# PCIe-JTAG.net
KiCad netlist of a schematic drawn in Altium Designer
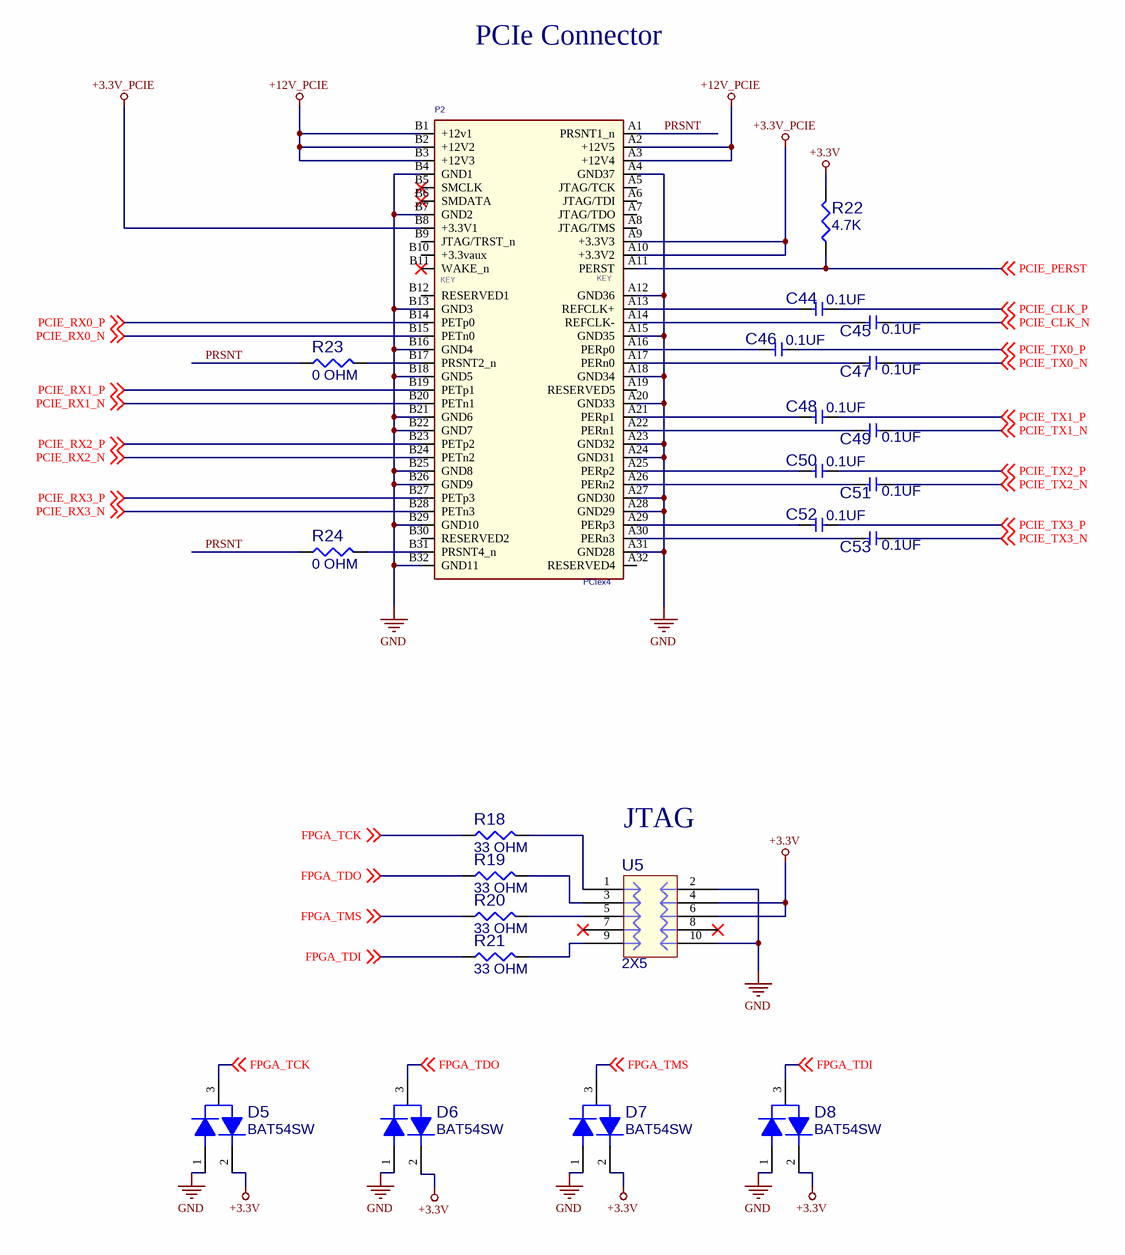
[diagram p0: PCIe-JTAG.SchDoc]

(export (version "E")
  (design (tool "Eeschema 10.0.6"))
  (components
    (comp (ref "C44")
      (value "0.1UF")
      (footprint "CAPC1005X06N")
      (description "CAP, CER, 0.1UF, 50V, 10%, X7R, AEC-Q200, 0402")
      (fields
        (field (name "MFG PART NUM") "CGA2B3X7R1H104K050BB")
        (field (name "VALENTIUM PART NUM") "<VALENTIUM>")
      )
      (libsource (lib "Capacitors") (part "CAP_0402_0.1UF_50V"))
    )
    (comp (ref "C45")
      (value "0.1UF")
      (footprint "CAPC1005X06N")
      (description "CAP, CER, 0.1UF, 50V, 10%, X7R, AEC-Q200, 0402")
      (fields
        (field (name "MFG PART NUM") "CGA2B3X7R1H104K050BB")
        (field (name "VALENTIUM PART NUM") "<VALENTIUM>")
      )
      (libsource (lib "Capacitors") (part "CAP_0402_0.1UF_50V"))
    )
    (comp (ref "C46")
      (value "0.1UF")
      (footprint "CAPC1005X06N")
      (description "CAP, CER, 0.1UF, 50V, 10%, X7R, AEC-Q200, 0402")
      (fields
        (field (name "MFG PART NUM") "CGA2B3X7R1H104K050BB")
        (field (name "VALENTIUM PART NUM") "<VALENTIUM>")
      )
      (libsource (lib "Capacitors") (part "CAP_0402_0.1UF_50V"))
    )
    (comp (ref "C47")
      (value "0.1UF")
      (footprint "CAPC1005X06N")
      (description "CAP, CER, 0.1UF, 50V, 10%, X7R, AEC-Q200, 0402")
      (fields
        (field (name "MFG PART NUM") "CGA2B3X7R1H104K050BB")
        (field (name "VALENTIUM PART NUM") "<VALENTIUM>")
      )
      (libsource (lib "Capacitors") (part "CAP_0402_0.1UF_50V"))
    )
    (comp (ref "C48")
      (value "0.1UF")
      (footprint "CAPC1005X06N")
      (description "CAP, CER, 0.1UF, 50V, 10%, X7R, AEC-Q200, 0402")
      (fields
        (field (name "MFG PART NUM") "CGA2B3X7R1H104K050BB")
        (field (name "VALENTIUM PART NUM") "<VALENTIUM>")
      )
      (libsource (lib "Capacitors") (part "CAP_0402_0.1UF_50V"))
    )
    (comp (ref "C49")
      (value "0.1UF")
      (footprint "CAPC1005X06N")
      (description "CAP, CER, 0.1UF, 50V, 10%, X7R, AEC-Q200, 0402")
      (fields
        (field (name "MFG PART NUM") "CGA2B3X7R1H104K050BB")
        (field (name "VALENTIUM PART NUM") "<VALENTIUM>")
      )
      (libsource (lib "Capacitors") (part "CAP_0402_0.1UF_50V"))
    )
    (comp (ref "C50")
      (value "0.1UF")
      (footprint "CAPC1005X06N")
      (description "CAP, CER, 0.1UF, 50V, 10%, X7R, AEC-Q200, 0402")
      (fields
        (field (name "MFG PART NUM") "CGA2B3X7R1H104K050BB")
        (field (name "VALENTIUM PART NUM") "<VALENTIUM>")
      )
      (libsource (lib "Capacitors") (part "CAP_0402_0.1UF_50V"))
    )
    (comp (ref "C51")
      (value "0.1UF")
      (footprint "CAPC1005X06N")
      (description "CAP, CER, 0.1UF, 50V, 10%, X7R, AEC-Q200, 0402")
      (fields
        (field (name "MFG PART NUM") "CGA2B3X7R1H104K050BB")
        (field (name "VALENTIUM PART NUM") "<VALENTIUM>")
      )
      (libsource (lib "Capacitors") (part "CAP_0402_0.1UF_50V"))
    )
    (comp (ref "C52")
      (value "0.1UF")
      (footprint "CAPC1005X06N")
      (description "CAP, CER, 0.1UF, 50V, 10%, X7R, AEC-Q200, 0402")
      (fields
        (field (name "MFG PART NUM") "CGA2B3X7R1H104K050BB")
        (field (name "VALENTIUM PART NUM") "<VALENTIUM>")
      )
      (libsource (lib "Capacitors") (part "CAP_0402_0.1UF_50V"))
    )
    (comp (ref "C53")
      (value "0.1UF")
      (footprint "CAPC1005X06N")
      (description "CAP, CER, 0.1UF, 50V, 10%, X7R, AEC-Q200, 0402")
      (fields
        (field (name "MFG PART NUM") "CGA2B3X7R1H104K050BB")
        (field (name "VALENTIUM PART NUM") "<VALENTIUM>")
      )
      (libsource (lib "Capacitors") (part "CAP_0402_0.1UF_50V"))
    )
    (comp (ref "D5")
      (value "BAT54SW")
      (footprint "SOT65P210X110-3N")
      (description "DIO, SCHOTTKY, BAT54S, DUAL SERIES, 30V, 200MA, SC-70")
      (fields (field (name "MFG PART NUM") "BAT54SWQ-7-F") (field (name "VALENTIUM PART NUM") "<VALENTIUM>"))
      (libsource (lib "Passives") (part "BAT54SW"))
    )
    (comp (ref "D6")
      (value "BAT54SW")
      (footprint "SOT65P210X110-3N")
      (description "DIO, SCHOTTKY, BAT54S, DUAL SERIES, 30V, 200MA, SC-70")
      (fields (field (name "MFG PART NUM") "BAT54SWQ-7-F") (field (name "VALENTIUM PART NUM") "<VALENTIUM>"))
      (libsource (lib "Passives") (part "BAT54SW"))
    )
    (comp (ref "D7")
      (value "BAT54SW")
      (footprint "SOT65P210X110-3N")
      (description "DIO, SCHOTTKY, BAT54S, DUAL SERIES, 30V, 200MA, SC-70")
      (fields (field (name "MFG PART NUM") "BAT54SWQ-7-F") (field (name "VALENTIUM PART NUM") "<VALENTIUM>"))
      (libsource (lib "Passives") (part "BAT54SW"))
    )
    (comp (ref "D8")
      (value "BAT54SW")
      (footprint "SOT65P210X110-3N")
      (description "DIO, SCHOTTKY, BAT54S, DUAL SERIES, 30V, 200MA, SC-70")
      (fields (field (name "MFG PART NUM") "BAT54SWQ-7-F") (field (name "VALENTIUM PART NUM") "<VALENTIUM>"))
      (libsource (lib "Passives") (part "BAT54SW"))
    )
    (comp (ref "P2")
      (value "PCIex4")
      (footprint "PCIE_4LANE_EDGE")
      (description "PCIE x4 Edge Connector,OrCAD Symbol,NC")
      (fields (field (name "PART NUMBER") "451") (field (name "MANUFACTURER") "NA"))
      (libsource (lib "Connectors") (part "PCIex4"))
    )
    (comp (ref "R18")
      (value "33 OHM")
      (footprint "RESC2012X50N")
      (description "RES, 33 OHM, 1%, 1/8W, TF, 0805")
      (fields
        (field (name "MFG PART NUM") "CRCW080533R0FKEA")
        (field (name "VELENTIUM PART NUM") "<VELENTIUM>")
      )
      (libsource (lib "Resistors") (part "RES_0805_33"))
    )
    (comp (ref "R19")
      (value "33 OHM")
      (footprint "RESC2012X50N")
      (description "RES, 33 OHM, 1%, 1/8W, TF, 0805")
      (fields
        (field (name "MFG PART NUM") "CRCW080533R0FKEA")
        (field (name "VELENTIUM PART NUM") "<VELENTIUM>")
      )
      (libsource (lib "Resistors") (part "RES_0805_33"))
    )
    (comp (ref "R20")
      (value "33 OHM")
      (footprint "RESC2012X50N")
      (description "RES, 33 OHM, 1%, 1/8W, TF, 0805")
      (fields
        (field (name "MFG PART NUM") "CRCW080533R0FKEA")
        (field (name "VELENTIUM PART NUM") "<VELENTIUM>")
      )
      (libsource (lib "Resistors") (part "RES_0805_33"))
    )
    (comp (ref "R21")
      (value "33 OHM")
      (footprint "RESC2012X50N")
      (description "RES, 33 OHM, 1%, 1/8W, TF, 0805")
      (fields
        (field (name "MFG PART NUM") "CRCW080533R0FKEA")
        (field (name "VELENTIUM PART NUM") "<VELENTIUM>")
      )
      (libsource (lib "Resistors") (part "RES_0805_33"))
    )
    (comp (ref "R22")
      (value "4.7K")
      (footprint "RESC1608X50N")
      (description "RES, 4.7K, 1%, 1/10W, TF, 0603")
      (fields (field (name "MFG PART NUM") "ERJ-3EKF4701V") (field (name "VELENTIUM PART NUM") "<VELENTIUM>"))
      (libsource (lib "Resistors") (part "RES_0603_4.7K"))
    )
    (comp (ref "R23")
      (value "0 OHM")
      (footprint "RESC1005X04N")
      (description "RES, 0. OHM, 1%, 1/16W, TF, AEC-Q200, 0402")
      (fields (field (name "MFG PART NUM") "ERJ-2GE0R00X") (field (name "VELENTIUM PART NUM") "<VELENTIUM>"))
      (libsource (lib "Resistors") (part "RES_0402_0"))
    )
    (comp (ref "R24")
      (value "0 OHM")
      (footprint "RESC1005X04N")
      (description "RES, 0. OHM, 1%, 1/16W, TF, AEC-Q200, 0402")
      (fields (field (name "MFG PART NUM") "ERJ-2GE0R00X") (field (name "VELENTIUM PART NUM") "<VELENTIUM>"))
      (libsource (lib "Resistors") (part "RES_0402_0"))
    )
    (comp (ref "U5")
      (value "2X5")
      (footprint "SAMTEC_HTST-105-01-L-DV-A")
      (description "CONN, HDR, 2X5, VERT, 0.1IN  SHROUDED, SMT, HTSH SERIES")
      (fields
        (field (name "MFG PART NUM") "HTST-105-01-L-DV-A")
        (field (name "VALENTIUM PART NUM") "<VALENTIUM>")
      )
      (libsource (lib "Connectors") (part "SAMTEC-HTSH-105-01-L-DV"))
    )
  )
  (nets
    (net (code "1") (name "+3.3V") (class "Default")
      (node (ref "D5") (pin "2") (pinfunction "2_2") (pintype "passive"))
      (node (ref "D6") (pin "2") (pinfunction "2_2") (pintype "passive"))
      (node (ref "D7") (pin "2") (pinfunction "2_2") (pintype "passive"))
      (node (ref "D8") (pin "2") (pinfunction "2_2") (pintype "passive"))
      (node (ref "R22") (pin "2") (pinfunction "2_2") (pintype "passive"))
      (node (ref "U5") (pin "4") (pinfunction "P4_4") (pintype "passive"))
      (node (ref "U5") (pin "6") (pinfunction "P6_6") (pintype "passive"))
    )
    (net (code "2") (name "+3.3V_PCIE") (class "Default")
      (node (ref "P2") (pin "A10") (pinfunction "+3.3V2_A10") (pintype "passive"))
      (node (ref "P2") (pin "A9") (pinfunction "+3.3V3_A9") (pintype "passive"))
      (node (ref "P2") (pin "B8") (pinfunction "+3.3V1_B8") (pintype "power_in"))
    )
    (net (code "3") (name "+12V_PCIE") (class "Default")
      (node (ref "P2") (pin "A2") (pinfunction "+12V5_A2") (pintype "passive"))
      (node (ref "P2") (pin "A3") (pinfunction "+12V4_A3") (pintype "passive"))
      (node (ref "P2") (pin "B1") (pinfunction "+12v1_B1") (pintype "power_in"))
      (node (ref "P2") (pin "B2") (pinfunction "+12V2_B2") (pintype "power_in"))
      (node (ref "P2") (pin "B3") (pinfunction "+12V3_B3") (pintype "power_in"))
    )
    (net (code "4") (name "/PRSNT") (class "Default")
      (node (ref "P2") (pin "A1") (pinfunction "PRSNT1_n_A1") (pintype "passive"))
      (node (ref "R23") (pin "1") (pinfunction "1_1") (pintype "passive"))
      (node (ref "R24") (pin "1") (pinfunction "1_1") (pintype "passive"))
    )
    (net (code "5") (name "FPGA_TCK") (class "Default")
      (node (ref "D5") (pin "3") (pinfunction "3_3") (pintype "passive"))
      (node (ref "R18") (pin "1") (pinfunction "1_1") (pintype "passive"))
    )
    (net (code "6") (name "FPGA_TDI") (class "Default")
      (node (ref "D8") (pin "3") (pinfunction "3_3") (pintype "passive"))
      (node (ref "R21") (pin "1") (pinfunction "1_1") (pintype "passive"))
    )
    (net (code "7") (name "FPGA_TDO") (class "Default")
      (node (ref "D6") (pin "3") (pinfunction "3_3") (pintype "passive"))
      (node (ref "R19") (pin "1") (pinfunction "1_1") (pintype "passive"))
    )
    (net (code "8") (name "FPGA_TMS") (class "Default")
      (node (ref "D7") (pin "3") (pinfunction "3_3") (pintype "passive"))
      (node (ref "R20") (pin "1") (pinfunction "1_1") (pintype "passive"))
    )
    (net (code "9") (name "GND") (class "Default")
      (node (ref "D5") (pin "1") (pinfunction "1_1") (pintype "passive"))
      (node (ref "D6") (pin "1") (pinfunction "1_1") (pintype "passive"))
      (node (ref "D7") (pin "1") (pinfunction "1_1") (pintype "passive"))
      (node (ref "D8") (pin "1") (pinfunction "1_1") (pintype "passive"))
      (node (ref "P2") (pin "A12") (pinfunction "GND36_A12") (pintype "power_in"))
      (node (ref "P2") (pin "A15") (pinfunction "GND35_A15") (pintype "power_in"))
      (node (ref "P2") (pin "A18") (pinfunction "GND34_A18") (pintype "power_in"))
      (node (ref "P2") (pin "A20") (pinfunction "GND33_A20") (pintype "power_in"))
      (node (ref "P2") (pin "A23") (pinfunction "GND32_A23") (pintype "power_in"))
      (node (ref "P2") (pin "A24") (pinfunction "GND31_A24") (pintype "power_in"))
      (node (ref "P2") (pin "A27") (pinfunction "GND30_A27") (pintype "power_in"))
      (node (ref "P2") (pin "A28") (pinfunction "GND29_A28") (pintype "power_in"))
      (node (ref "P2") (pin "A31") (pinfunction "GND28_A31") (pintype "power_in"))
      (node (ref "P2") (pin "A4") (pinfunction "GND37_A4") (pintype "power_in"))
      (node (ref "P2") (pin "B13") (pinfunction "GND3_B13") (pintype "power_in"))
      (node (ref "P2") (pin "B16") (pinfunction "GND4_B16") (pintype "power_in"))
      (node (ref "P2") (pin "B18") (pinfunction "GND5_B18") (pintype "power_in"))
      (node (ref "P2") (pin "B21") (pinfunction "GND6_B21") (pintype "power_in"))
      (node (ref "P2") (pin "B22") (pinfunction "GND7_B22") (pintype "power_in"))
      (node (ref "P2") (pin "B25") (pinfunction "GND8_B25") (pintype "power_in"))
      (node (ref "P2") (pin "B26") (pinfunction "GND9_B26") (pintype "power_in"))
      (node (ref "P2") (pin "B29") (pinfunction "GND10_B29") (pintype "power_in"))
      (node (ref "P2") (pin "B32") (pinfunction "GND11_B32") (pintype "power_in"))
      (node (ref "P2") (pin "B4") (pinfunction "GND1_B4") (pintype "power_in"))
      (node (ref "P2") (pin "B7") (pinfunction "GND2_B7") (pintype "power_in"))
      (node (ref "U5") (pin "10") (pinfunction "P10_10") (pintype "passive"))
      (node (ref "U5") (pin "2") (pinfunction "P2_2") (pintype "passive"))
    )
    (net (code "10") (name "Net-(P2-PERn0)") (class "Default")
      (node (ref "C47") (pin "1") (pinfunction "1_1") (pintype "passive"))
      (node (ref "P2") (pin "A17") (pinfunction "PERn0_A17") (pintype "passive"))
    )
    (net (code "11") (name "Net-(P2-PERn1)") (class "Default")
      (node (ref "C49") (pin "1") (pinfunction "1_1") (pintype "passive"))
      (node (ref "P2") (pin "A22") (pinfunction "PERn1_A22") (pintype "passive"))
    )
    (net (code "12") (name "Net-(P2-PERn2)") (class "Default")
      (node (ref "C51") (pin "1") (pinfunction "1_1") (pintype "passive"))
      (node (ref "P2") (pin "A26") (pinfunction "PERn2_A26") (pintype "passive"))
    )
    (net (code "13") (name "Net-(P2-PERn3)") (class "Default")
      (node (ref "C53") (pin "1") (pinfunction "1_1") (pintype "passive"))
      (node (ref "P2") (pin "A30") (pinfunction "PERn3_A30") (pintype "passive"))
    )
    (net (code "14") (name "Net-(P2-PERp0)") (class "Default")
      (node (ref "C46") (pin "1") (pinfunction "1_1") (pintype "passive"))
      (node (ref "P2") (pin "A16") (pinfunction "PERp0_A16") (pintype "passive"))
    )
    (net (code "15") (name "Net-(P2-PERp1)") (class "Default")
      (node (ref "C48") (pin "1") (pinfunction "1_1") (pintype "passive"))
      (node (ref "P2") (pin "A21") (pinfunction "PERp1_A21") (pintype "passive"))
    )
    (net (code "16") (name "Net-(P2-PERp2)") (class "Default")
      (node (ref "C50") (pin "1") (pinfunction "1_1") (pintype "passive"))
      (node (ref "P2") (pin "A25") (pinfunction "PERp2_A25") (pintype "passive"))
    )
    (net (code "17") (name "Net-(P2-PERp3)") (class "Default")
      (node (ref "C52") (pin "1") (pinfunction "1_1") (pintype "passive"))
      (node (ref "P2") (pin "A29") (pinfunction "PERp3_A29") (pintype "passive"))
    )
    (net (code "18") (name "Net-(P2-PRSNT2_n)") (class "Default")
      (node (ref "P2") (pin "B17") (pinfunction "PRSNT2_n_B17") (pintype "passive"))
      (node (ref "R23") (pin "2") (pinfunction "2_2") (pintype "passive"))
    )
    (net (code "19") (name "Net-(P2-PRSNT4_n)") (class "Default")
      (node (ref "P2") (pin "B31") (pinfunction "PRSNT4_n_B31") (pintype "passive"))
      (node (ref "R24") (pin "2") (pinfunction "2_2") (pintype "passive"))
    )
    (net (code "20") (name "Net-(P2-REFCLK+)") (class "Default")
      (node (ref "C44") (pin "1") (pinfunction "1_1") (pintype "passive"))
      (node (ref "P2") (pin "A13") (pinfunction "REFCLK+_A13") (pintype "passive"))
    )
    (net (code "21") (name "Net-(P2-REFCLK-)") (class "Default")
      (node (ref "C45") (pin "1") (pinfunction "1_1") (pintype "passive"))
      (node (ref "P2") (pin "A14") (pinfunction "REFCLK-_A14") (pintype "passive"))
    )
    (net (code "22") (name "Net-(U5-P1)") (class "Default")
      (node (ref "R18") (pin "2") (pinfunction "2_2") (pintype "passive"))
      (node (ref "U5") (pin "1") (pinfunction "P1_1") (pintype "passive"))
    )
    (net (code "23") (name "Net-(U5-P3)") (class "Default")
      (node (ref "R19") (pin "2") (pinfunction "2_2") (pintype "passive"))
      (node (ref "U5") (pin "3") (pinfunction "P3_3") (pintype "passive"))
    )
    (net (code "24") (name "Net-(U5-P5)") (class "Default")
      (node (ref "R20") (pin "2") (pinfunction "2_2") (pintype "passive"))
      (node (ref "U5") (pin "5") (pinfunction "P5_5") (pintype "passive"))
    )
    (net (code "25") (name "Net-(U5-P9)") (class "Default")
      (node (ref "R21") (pin "2") (pinfunction "2_2") (pintype "passive"))
      (node (ref "U5") (pin "9") (pinfunction "P9_9") (pintype "passive"))
    )
    (net (code "26") (name "PCIE_CLK_N") (class "Default")
      (node (ref "C45") (pin "2") (pinfunction "2_2") (pintype "passive"))
    )
    (net (code "27") (name "PCIE_CLK_P") (class "Default")
      (node (ref "C44") (pin "2") (pinfunction "2_2") (pintype "passive"))
    )
    (net (code "28") (name "PCIE_PERST") (class "Default")
      (node (ref "P2") (pin "A11") (pinfunction "PERST_A11") (pintype "passive"))
      (node (ref "R22") (pin "1") (pinfunction "1_1") (pintype "passive"))
    )
    (net (code "29") (name "PCIE_RX0_N") (class "Default")
      (node (ref "P2") (pin "B15") (pinfunction "PETn0_B15") (pintype "passive"))
    )
    (net (code "30") (name "PCIE_RX0_P") (class "Default")
      (node (ref "P2") (pin "B14") (pinfunction "PETp0_B14") (pintype "passive"))
    )
    (net (code "31") (name "PCIE_RX1_N") (class "Default")
      (node (ref "P2") (pin "B20") (pinfunction "PETn1_B20") (pintype "passive"))
    )
    (net (code "32") (name "PCIE_RX1_P") (class "Default")
      (node (ref "P2") (pin "B19") (pinfunction "PETp1_B19") (pintype "passive"))
    )
    (net (code "33") (name "PCIE_RX2_N") (class "Default")
      (node (ref "P2") (pin "B24") (pinfunction "PETn2_B24") (pintype "passive"))
    )
    (net (code "34") (name "PCIE_RX2_P") (class "Default")
      (node (ref "P2") (pin "B23") (pinfunction "PETp2_B23") (pintype "passive"))
    )
    (net (code "35") (name "PCIE_RX3_N") (class "Default")
      (node (ref "P2") (pin "B28") (pinfunction "PETn3_B28") (pintype "passive"))
    )
    (net (code "36") (name "PCIE_RX3_P") (class "Default")
      (node (ref "P2") (pin "B27") (pinfunction "PETp3_B27") (pintype "passive"))
    )
    (net (code "37") (name "PCIE_TX0_N") (class "Default")
      (node (ref "C47") (pin "2") (pinfunction "2_2") (pintype "passive"))
    )
    (net (code "38") (name "PCIE_TX0_P") (class "Default")
      (node (ref "C46") (pin "2") (pinfunction "2_2") (pintype "passive"))
    )
    (net (code "39") (name "PCIE_TX1_N") (class "Default")
      (node (ref "C49") (pin "2") (pinfunction "2_2") (pintype "passive"))
    )
    (net (code "40") (name "PCIE_TX1_P") (class "Default")
      (node (ref "C48") (pin "2") (pinfunction "2_2") (pintype "passive"))
    )
    (net (code "41") (name "PCIE_TX2_N") (class "Default")
      (node (ref "C51") (pin "2") (pinfunction "2_2") (pintype "passive"))
    )
    (net (code "42") (name "PCIE_TX2_P") (class "Default")
      (node (ref "C50") (pin "2") (pinfunction "2_2") (pintype "passive"))
    )
    (net (code "43") (name "PCIE_TX3_N") (class "Default")
      (node (ref "C53") (pin "2") (pinfunction "2_2") (pintype "passive"))
    )
    (net (code "44") (name "PCIE_TX3_P") (class "Default")
      (node (ref "C52") (pin "2") (pinfunction "2_2") (pintype "passive"))
    )
    (net (code "45") (name "unconnected-(P2-+3.3vaux-PadB10)") (class "Default")
      (node (ref "P2") (pin "B10") (pinfunction "+3.3vaux_B10") (pintype "passive"))
    )
    (net (code "46") (name "unconnected-(P2-JTAG{slash}TCK-PadA5)") (class "Default")
      (node (ref "P2") (pin "A5") (pinfunction "JTAG/TCK_A5") (pintype "passive"))
    )
    (net (code "47") (name "unconnected-(P2-JTAG{slash}TDI-PadA6)") (class "Default")
      (node (ref "P2") (pin "A6") (pinfunction "JTAG/TDI_A6") (pintype "passive"))
    )
    (net (code "48") (name "unconnected-(P2-JTAG{slash}TDO-PadA7)") (class "Default")
      (node (ref "P2") (pin "A7") (pinfunction "JTAG/TDO_A7") (pintype "passive"))
    )
    (net (code "49") (name "unconnected-(P2-JTAG{slash}TMS-PadA8)") (class "Default")
      (node (ref "P2") (pin "A8") (pinfunction "JTAG/TMS_A8") (pintype "passive"))
    )
    (net (code "50") (name "unconnected-(P2-JTAG{slash}TRST_n-PadB9)") (class "Default")
      (node (ref "P2") (pin "B9") (pinfunction "JTAG/TRST_n_B9") (pintype "passive"))
    )
    (net (code "51") (name "unconnected-(P2-RESERVED1-PadB12)") (class "Default")
      (node (ref "P2") (pin "B12") (pinfunction "RESERVED1_B12") (pintype "passive"))
    )
    (net (code "52") (name "unconnected-(P2-RESERVED2-PadB30)") (class "Default")
      (node (ref "P2") (pin "B30") (pinfunction "RESERVED2_B30") (pintype "passive"))
    )
    (net (code "53") (name "unconnected-(P2-RESERVED4-PadA32)") (class "Default")
      (node (ref "P2") (pin "A32") (pinfunction "RESERVED4_A32") (pintype "passive"))
    )
    (net (code "54") (name "unconnected-(P2-RESERVED5-PadA19)") (class "Default")
      (node (ref "P2") (pin "A19") (pinfunction "RESERVED5_A19") (pintype "passive"))
    )
    (net (code "55") (name "unconnected-(P2-SMCLK-PadB5)") (class "Default")
      (node (ref "P2") (pin "B5") (pinfunction "SMCLK_B5") (pintype "passive+no_connect"))
    )
    (net (code "56") (name "unconnected-(P2-SMDATA-PadB6)") (class "Default")
      (node (ref "P2") (pin "B6") (pinfunction "SMDATA_B6") (pintype "passive+no_connect"))
    )
    (net (code "57") (name "unconnected-(P2-WAKE_n-PadB11)") (class "Default")
      (node (ref "P2") (pin "B11") (pinfunction "WAKE_n_B11") (pintype "passive+no_connect"))
    )
    (net (code "58") (name "unconnected-(U5-P7-Pad7)") (class "Default")
      (node (ref "U5") (pin "7") (pinfunction "P7_7") (pintype "passive+no_connect"))
    )
    (net (code "59") (name "unconnected-(U5-P8-Pad8)") (class "Default")
      (node (ref "U5") (pin "8") (pinfunction "P8_8") (pintype "passive+no_connect"))
    )
  )
)
